# MCU.net
KiCad netlist of a schematic drawn in Altium Designer
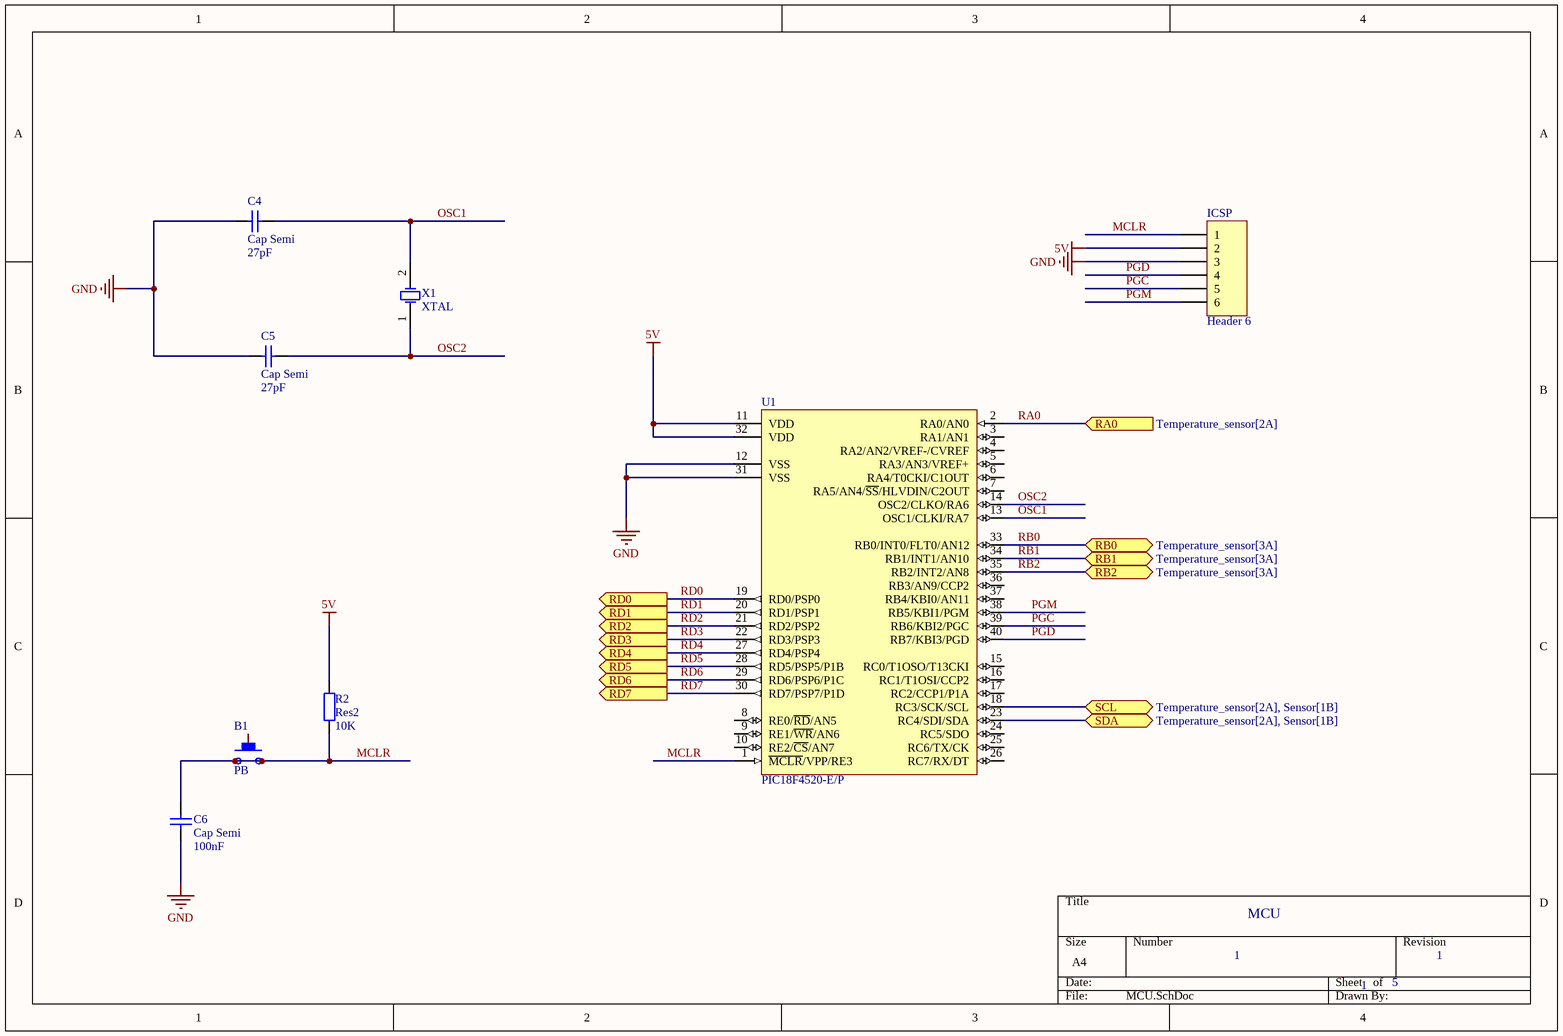
[diagram p0: MCU.SchDoc]

(export (version "E")
  (design (tool "Eeschema 10.0.6"))
  (components
    (comp (ref "B1") (value "PB") (footprint "Push button") (libsource (lib "PB") (part "PB")))
    (comp (ref "C4")
      (value "Cap Semi")
      (footprint "C1206")
      (description "Capacitor (Semiconductor SIM Model)")
      (fields (field (name "ALTIUM_VALUE") "27pF") (field (name "PUBLISHER") "Altium Limited"))
      (libsource (lib "Miscellaneous Devices") (part "Cap Semi"))
    )
    (comp (ref "C5")
      (value "Cap Semi")
      (footprint "C1206")
      (description "Capacitor (Semiconductor SIM Model)")
      (fields (field (name "ALTIUM_VALUE") "27pF") (field (name "PUBLISHER") "Altium Limited"))
      (libsource (lib "Miscellaneous Devices") (part "Cap Semi"))
    )
    (comp (ref "C6")
      (value "Cap Semi")
      (footprint "C1206")
      (description "Capacitor (Semiconductor SIM Model)")
      (fields (field (name "ALTIUM_VALUE") "100nF") (field (name "PUBLISHER") "Altium Limited"))
      (libsource (lib "Miscellaneous Devices") (part "Cap Semi"))
    )
    (comp (ref "ICSP")
      (value "Header 6")
      (footprint "HDR1X6")
      (description "Header, 6-Pin")
      (fields (field (name "PUBLISHER") "Altium Limited"))
      (libsource (lib "Miscellaneous Connectors") (part "Header 6"))
    )
    (comp (ref "R2")
      (value "Res2")
      (footprint "0805")
      (description "Resistor")
      (fields (field (name "ALTIUM_VALUE") "10K") (field (name "PUBLISHER") "Altium Limited"))
      (libsource (lib "Miscellaneous Devices") (part "Res2"))
    )
    (comp (ref "U1")
      (value "PIC18F4520-E/P")
      (footprint "PDIP600-P40")
      (fields (field (name "PUBLISHER") "Altium Limited"))
      (libsource (lib "Microchip Microcontroller 8-Bit PIC18") (part "PIC18F4520-E/P"))
    )
    (comp (ref "X1")
      (value "XTAL")
      (footprint "R38")
      (description "Crystal Oscillator")
      (fields (field (name "PUBLISHER") "Altium Limited"))
      (libsource (lib "Miscellaneous Devices") (part "XTAL"))
    )
  )
  (nets
    (net (code "1") (name "/MCLR") (class "Default")
      (node (ref "B1") (pin "0") (pinfunction "0_0") (pintype "passive"))
      (node (ref "B1") (pin "1") (pinfunction "1_1") (pintype "passive"))
      (node (ref "C6") (pin "1") (pinfunction "1_1") (pintype "passive"))
      (node (ref "ICSP") (pin "1") (pinfunction "1_1") (pintype "passive"))
      (node (ref "R2") (pin "1") (pinfunction "1_1") (pintype "passive"))
      (node (ref "U1") (pin "1") (pinfunction "~{MCLR}/VPP/RE3_1") (pintype "input"))
    )
    (net (code "2") (name "/OSC1") (class "Default")
      (node (ref "C4") (pin "2") (pinfunction "2_2") (pintype "passive"))
      (node (ref "U1") (pin "13") (pinfunction "OSC1/CLKI/RA7_13") (pintype "bidirectional"))
      (node (ref "X1") (pin "2") (pinfunction "OSC2_2") (pintype "passive"))
    )
    (net (code "3") (name "/OSC2") (class "Default")
      (node (ref "C5") (pin "2") (pinfunction "2_2") (pintype "passive"))
      (node (ref "U1") (pin "14") (pinfunction "OSC2/CLKO/RA6_14") (pintype "bidirectional"))
      (node (ref "X1") (pin "1") (pinfunction "OSC1_1") (pintype "passive"))
    )
    (net (code "4") (name "/PGC") (class "Default")
      (node (ref "ICSP") (pin "5") (pinfunction "5_5") (pintype "passive"))
      (node (ref "U1") (pin "39") (pinfunction "RB6/KBI2/PGC_39") (pintype "bidirectional"))
    )
    (net (code "5") (name "/PGD") (class "Default")
      (node (ref "ICSP") (pin "4") (pinfunction "4_4") (pintype "passive"))
      (node (ref "U1") (pin "40") (pinfunction "RB7/KBI3/PGD_40") (pintype "bidirectional"))
    )
    (net (code "6") (name "/PGM") (class "Default")
      (node (ref "ICSP") (pin "6") (pinfunction "6_6") (pintype "passive"))
      (node (ref "U1") (pin "38") (pinfunction "RB5/KBI1/PGM_38") (pintype "bidirectional"))
    )
    (net (code "7") (name "/RA0") (class "Default")
      (node (ref "U1") (pin "2") (pinfunction "RA0/AN0_2") (pintype "input"))
    )
    (net (code "8") (name "/RB0") (class "Default")
      (node (ref "U1") (pin "33") (pinfunction "RB0/INT0/FLT0/AN12_33") (pintype "bidirectional"))
    )
    (net (code "9") (name "/RB1") (class "Default")
      (node (ref "U1") (pin "34") (pinfunction "RB1/INT1/AN10_34") (pintype "bidirectional"))
    )
    (net (code "10") (name "/RB2") (class "Default")
      (node (ref "U1") (pin "35") (pinfunction "RB2/INT2/AN8_35") (pintype "bidirectional"))
    )
    (net (code "11") (name "/RD0") (class "Default")
      (node (ref "U1") (pin "19") (pinfunction "RD0/PSP0_19") (pintype "output"))
    )
    (net (code "12") (name "/RD1") (class "Default")
      (node (ref "U1") (pin "20") (pinfunction "RD1/PSP1_20") (pintype "output"))
    )
    (net (code "13") (name "/RD2") (class "Default")
      (node (ref "U1") (pin "21") (pinfunction "RD2/PSP2_21") (pintype "output"))
    )
    (net (code "14") (name "/RD3") (class "Default")
      (node (ref "U1") (pin "22") (pinfunction "RD3/PSP3_22") (pintype "output"))
    )
    (net (code "15") (name "/RD4") (class "Default")
      (node (ref "U1") (pin "27") (pinfunction "RD4/PSP4_27") (pintype "output"))
    )
    (net (code "16") (name "/RD5") (class "Default")
      (node (ref "U1") (pin "28") (pinfunction "RD5/PSP5/P1B_28") (pintype "output"))
    )
    (net (code "17") (name "/RD6") (class "Default")
      (node (ref "U1") (pin "29") (pinfunction "RD6/PSP6/P1C_29") (pintype "output"))
    )
    (net (code "18") (name "/RD7") (class "Default")
      (node (ref "U1") (pin "30") (pinfunction "RD7/PSP7/P1D_30") (pintype "output"))
    )
    (net (code "19") (name "/SCL") (class "Default")
      (node (ref "U1") (pin "18") (pinfunction "RC3/SCK/SCL_18") (pintype "bidirectional"))
    )
    (net (code "20") (name "/SDA") (class "Default")
      (node (ref "U1") (pin "23") (pinfunction "RC4/SDI/SDA_23") (pintype "bidirectional"))
    )
    (net (code "21") (name "5V") (class "Default")
      (node (ref "ICSP") (pin "2") (pinfunction "2_2") (pintype "passive"))
      (node (ref "R2") (pin "2") (pinfunction "2_2") (pintype "passive"))
      (node (ref "U1") (pin "11") (pinfunction "VDD_11") (pintype "power_in"))
      (node (ref "U1") (pin "32") (pinfunction "VDD_32") (pintype "power_in"))
    )
    (net (code "22") (name "GND") (class "Default")
      (node (ref "C4") (pin "1") (pinfunction "1_1") (pintype "passive"))
      (node (ref "C5") (pin "1") (pinfunction "1_1") (pintype "passive"))
      (node (ref "C6") (pin "2") (pinfunction "2_2") (pintype "passive"))
      (node (ref "ICSP") (pin "3") (pinfunction "3_3") (pintype "passive"))
      (node (ref "U1") (pin "12") (pinfunction "VSS_12") (pintype "power_in"))
      (node (ref "U1") (pin "31") (pinfunction "VSS_31") (pintype "power_in"))
    )
    (net (code "23") (name "unconnected-(U1-RA1{slash}AN1-Pad3)") (class "Default")
      (node (ref "U1") (pin "3") (pinfunction "RA1/AN1_3") (pintype "bidirectional"))
    )
    (net (code "24") (name "unconnected-(U1-RA2{slash}AN2{slash}VREF-{slash}CVREF-Pad4)") (class "Default")
      (node (ref "U1") (pin "4") (pinfunction "RA2/AN2/VREF-/CVREF_4") (pintype "bidirectional"))
    )
    (net (code "25") (name "unconnected-(U1-RA3{slash}AN3{slash}VREF+-Pad5)") (class "Default")
      (node (ref "U1") (pin "5") (pinfunction "RA3/AN3/VREF+_5") (pintype "bidirectional"))
    )
    (net (code "26") (name "unconnected-(U1-RA4{slash}T0CKI{slash}C1OUT-Pad6)") (class "Default")
      (node (ref "U1") (pin "6") (pinfunction "RA4/T0CKI/C1OUT_6") (pintype "bidirectional"))
    )
    (net (code "27") (name "unconnected-(U1-RA5{slash}AN4{slash}~{SS}{slash}HLVDIN{slash}C2OUT-Pad7)") (class "Default")
      (node (ref "U1") (pin "7") (pinfunction "RA5/AN4/~{SS}/HLVDIN/C2OUT_7") (pintype "bidirectional"))
    )
    (net (code "28") (name "unconnected-(U1-RB3{slash}AN9{slash}CCP2-Pad36)") (class "Default")
      (node (ref "U1") (pin "36") (pinfunction "RB3/AN9/CCP2_36") (pintype "bidirectional"))
    )
    (net (code "29") (name "unconnected-(U1-RB4{slash}KBI0{slash}AN11-Pad37)") (class "Default")
      (node (ref "U1") (pin "37") (pinfunction "RB4/KBI0/AN11_37") (pintype "bidirectional"))
    )
    (net (code "30") (name "unconnected-(U1-RC0{slash}T1OSO{slash}T13CKI-Pad15)") (class "Default")
      (node (ref "U1") (pin "15") (pinfunction "RC0/T1OSO/T13CKI_15") (pintype "bidirectional"))
    )
    (net (code "31") (name "unconnected-(U1-RC1{slash}T1OSI{slash}CCP2-Pad16)") (class "Default")
      (node (ref "U1") (pin "16") (pinfunction "RC1/T1OSI/CCP2_16") (pintype "bidirectional"))
    )
    (net (code "32") (name "unconnected-(U1-RC2{slash}CCP1{slash}P1A-Pad17)") (class "Default")
      (node (ref "U1") (pin "17") (pinfunction "RC2/CCP1/P1A_17") (pintype "bidirectional"))
    )
    (net (code "33") (name "unconnected-(U1-RC5{slash}SDO-Pad24)") (class "Default")
      (node (ref "U1") (pin "24") (pinfunction "RC5/SDO_24") (pintype "bidirectional"))
    )
    (net (code "34") (name "unconnected-(U1-RC6{slash}TX{slash}CK-Pad25)") (class "Default")
      (node (ref "U1") (pin "25") (pinfunction "RC6/TX/CK_25") (pintype "bidirectional"))
    )
    (net (code "35") (name "unconnected-(U1-RC7{slash}RX{slash}DT-Pad26)") (class "Default")
      (node (ref "U1") (pin "26") (pinfunction "RC7/RX/DT_26") (pintype "bidirectional"))
    )
    (net (code "36") (name "unconnected-(U1-RE0{slash}~{RD}{slash}AN5-Pad8)") (class "Default")
      (node (ref "U1") (pin "8") (pinfunction "RE0/~{RD}/AN5_8") (pintype "bidirectional"))
    )
    (net (code "37") (name "unconnected-(U1-RE1{slash}~{WR}{slash}AN6-Pad9)") (class "Default")
      (node (ref "U1") (pin "9") (pinfunction "RE1/~{WR}/AN6_9") (pintype "bidirectional"))
    )
    (net (code "38") (name "unconnected-(U1-RE2{slash}~{CS}{slash}AN7-Pad10)") (class "Default")
      (node (ref "U1") (pin "10") (pinfunction "RE2/~{CS}/AN7_10") (pintype "bidirectional"))
    )
  )
)
